# Bluetooth.net
KiCad netlist of a schematic drawn in Altium Designer
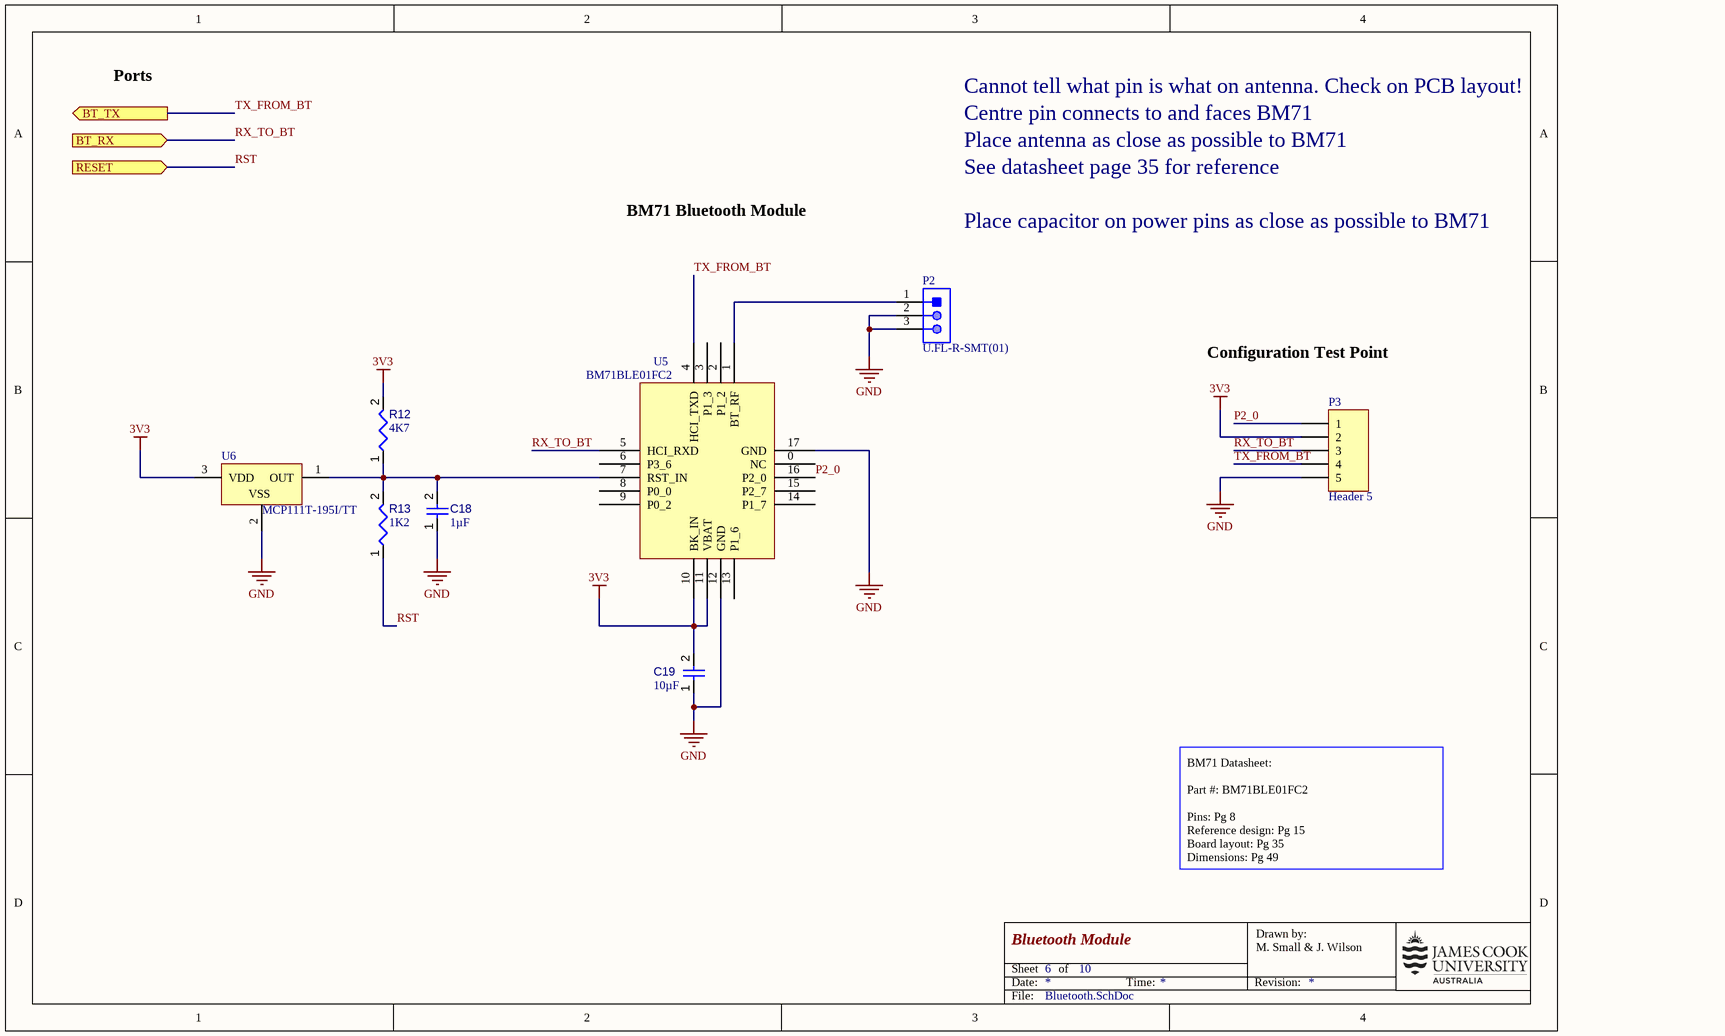
[diagram p0: Bluetooth.SchDoc]

(export (version "E")
  (design (tool "Eeschema 10.0.6"))
  (components
    (comp (ref "C18")
      (value "1µF")
      (footprint "CAPC0805(2012)145_L")
      (description "Chip Capacitor, 1µF +/-20%, 25V, 0805, Thickness 1.45 mm")
      (fields (field (name "TOLERANCE") "10%") (field (name "Comment") "Capacitor 1µF +/-20% 25V 0805"))
      (libsource (lib "James Cook University") (part "CAP-NP-2"))
    )
    (comp (ref "C19")
      (value "10µF")
      (footprint "CAPC0805(2012)145_L")
      (description "Chip Capacitor, 10µF +/-20%, 25V, 0805, Thickness 1.45 mm")
      (fields (field (name "TOLERANCE") "10%") (field (name "Comment") "Capacitor 10µF +/-20% 25V 0805"))
      (libsource (lib "James Cook University") (part "CAP-NP-2"))
    )
    (comp (ref "P2")
      (value "U.FL-R-SMT(01)")
      (footprint "HRS-U.FL-R-SMT(10)_V")
      (description "CONN RECPT ULTRA-MINI COAX SMD")
      (fields (field (name "MANUFACTURER") "Hirose Electric") (field (name "APPROVAL CATEGORY") "UL94V-0"))
      (libsource (lib "Altium Content Vault") (part "CN-1P-M-R3"))
    )
    (comp (ref "P3")
      (value "Header 5")
      (footprint "HDR1X5")
      (description "Header, 5-Pin")
      (fields (field (name "PUBLISHER") "Altium Limited"))
      (libsource (lib "Miscellaneous Connectors") (part "Header 5"))
    )
    (comp (ref "R12")
      (value "4K7")
      (footprint "RESC0805(2012)_L")
      (description "Chip Resistor, 4.7kOhms, +/-1%, 125 mW, -55 to 155 degC, 0805")
      (fields (field (name "POWER") "125mW") (field (name "TOLERANCE") "1%"))
      (libsource (lib "James Cook University") (part "RES-2"))
    )
    (comp (ref "R13")
      (value "1K2")
      (footprint "RESC0805(2012)_L")
      (description "1K2 0.125W 5% 0805 (2012 Metric)  SMD")
      (fields (field (name "POWER") "0.125W") (field (name "TOLERANCE") "5%"))
      (libsource (lib "James Cook University") (part "1KR5J"))
    )
    (comp (ref "U5")
      (value "BM71BLE01FC2")
      (footprint "BM71BLE01FC2")
      (description "Microchip BM71BLE01FC2 Bluetooth Low Energy (BLE) Module")
      (libsource (lib "CC3501_Misc_Symbols") (part "BM71BLE01FC2"))
    )
    (comp (ref "U6")
      (value "MCP111T-195I/TT")
      (footprint "SOT-23-TT3_M")
      (libsource (lib "Altium Content Vault") (part "PM-VLTD-MCP11X-SOT3"))
    )
  )
  (nets
    (net (code "1") (name "/P2_0") (class "Default")
      (node (ref "P3") (pin "1") (pinfunction "1_1") (pintype "passive"))
      (node (ref "U5") (pin "16") (pinfunction "P2_0_16") (pintype "passive"))
    )
    (net (code "2") (name "/RST") (class "Default")
      (node (ref "R13") (pin "1") (pinfunction "1_1") (pintype "passive"))
    )
    (net (code "3") (name "/RX_TO_BT") (class "Default")
      (node (ref "P3") (pin "3") (pinfunction "3_3") (pintype "passive"))
      (node (ref "U5") (pin "5") (pinfunction "HCI_RXD_5") (pintype "passive"))
    )
    (net (code "4") (name "/TX_FROM_BT") (class "Default")
      (node (ref "P3") (pin "4") (pinfunction "4_4") (pintype "passive"))
      (node (ref "U5") (pin "4") (pinfunction "HCI_TXD_4") (pintype "passive"))
    )
    (net (code "5") (name "3V3") (class "Default")
      (node (ref "C19") (pin "2") (pinfunction "2_2") (pintype "passive"))
      (node (ref "P3") (pin "2") (pinfunction "2_2") (pintype "passive"))
      (node (ref "R12") (pin "2") (pinfunction "2_2") (pintype "passive"))
      (node (ref "U5") (pin "10") (pinfunction "BK_IN_10") (pintype "passive"))
      (node (ref "U5") (pin "11") (pinfunction "VBAT_11") (pintype "passive"))
      (node (ref "U6") (pin "3") (pinfunction "VDD_3") (pintype "power_in"))
    )
    (net (code "6") (name "GND") (class "Default")
      (node (ref "C18") (pin "1") (pinfunction "1_1") (pintype "passive"))
      (node (ref "C19") (pin "1") (pinfunction "1_1") (pintype "passive"))
      (node (ref "P2") (pin "2") (pinfunction "2_2") (pintype "passive"))
      (node (ref "P2") (pin "3") (pinfunction "3_3") (pintype "passive"))
      (node (ref "P3") (pin "5") (pinfunction "5_5") (pintype "passive"))
      (node (ref "U5") (pin "12") (pinfunction "GND_12") (pintype "passive"))
      (node (ref "U5") (pin "17") (pinfunction "GND_17") (pintype "passive"))
      (node (ref "U6") (pin "2") (pinfunction "VSS_2") (pintype "power_in"))
    )
    (net (code "7") (name "Net-(U5-BT_RF)") (class "Default")
      (node (ref "P2") (pin "1") (pinfunction "1_1") (pintype "passive"))
      (node (ref "U5") (pin "1") (pinfunction "BT_RF_1") (pintype "passive"))
    )
    (net (code "8") (name "Net-(U5-RST_IN)") (class "Default")
      (node (ref "C18") (pin "2") (pinfunction "2_2") (pintype "passive"))
      (node (ref "R12") (pin "1") (pinfunction "1_1") (pintype "passive"))
      (node (ref "R13") (pin "2") (pinfunction "2_2") (pintype "passive"))
      (node (ref "U5") (pin "7") (pinfunction "RST_IN_7") (pintype "passive"))
      (node (ref "U6") (pin "1") (pinfunction "OUT_1") (pintype "power_in"))
    )
    (net (code "9") (name "unconnected-(U5-NC-Pad0)") (class "Default")
      (node (ref "U5") (pin "0") (pinfunction "NC_0") (pintype "passive"))
    )
    (net (code "10") (name "unconnected-(U5-P0_0-Pad8)") (class "Default")
      (node (ref "U5") (pin "8") (pinfunction "P0_0_8") (pintype "passive"))
    )
    (net (code "11") (name "unconnected-(U5-P0_2-Pad9)") (class "Default")
      (node (ref "U5") (pin "9") (pinfunction "P0_2_9") (pintype "passive"))
    )
    (net (code "12") (name "unconnected-(U5-P1_2-Pad2)") (class "Default")
      (node (ref "U5") (pin "2") (pinfunction "P1_2_2") (pintype "passive"))
    )
    (net (code "13") (name "unconnected-(U5-P1_3-Pad3)") (class "Default")
      (node (ref "U5") (pin "3") (pinfunction "P1_3_3") (pintype "passive"))
    )
    (net (code "14") (name "unconnected-(U5-P1_6-Pad13)") (class "Default")
      (node (ref "U5") (pin "13") (pinfunction "P1_6_13") (pintype "passive"))
    )
    (net (code "15") (name "unconnected-(U5-P1_7-Pad14)") (class "Default")
      (node (ref "U5") (pin "14") (pinfunction "P1_7_14") (pintype "passive"))
    )
    (net (code "16") (name "unconnected-(U5-P2_7-Pad15)") (class "Default")
      (node (ref "U5") (pin "15") (pinfunction "P2_7_15") (pintype "passive"))
    )
    (net (code "17") (name "unconnected-(U5-P3_6-Pad6)") (class "Default")
      (node (ref "U5") (pin "6") (pinfunction "P3_6_6") (pintype "passive"))
    )
  )
)
